# Prototyp-V-0_2.net
KiCad netlist of a schematic drawn in EAGLE
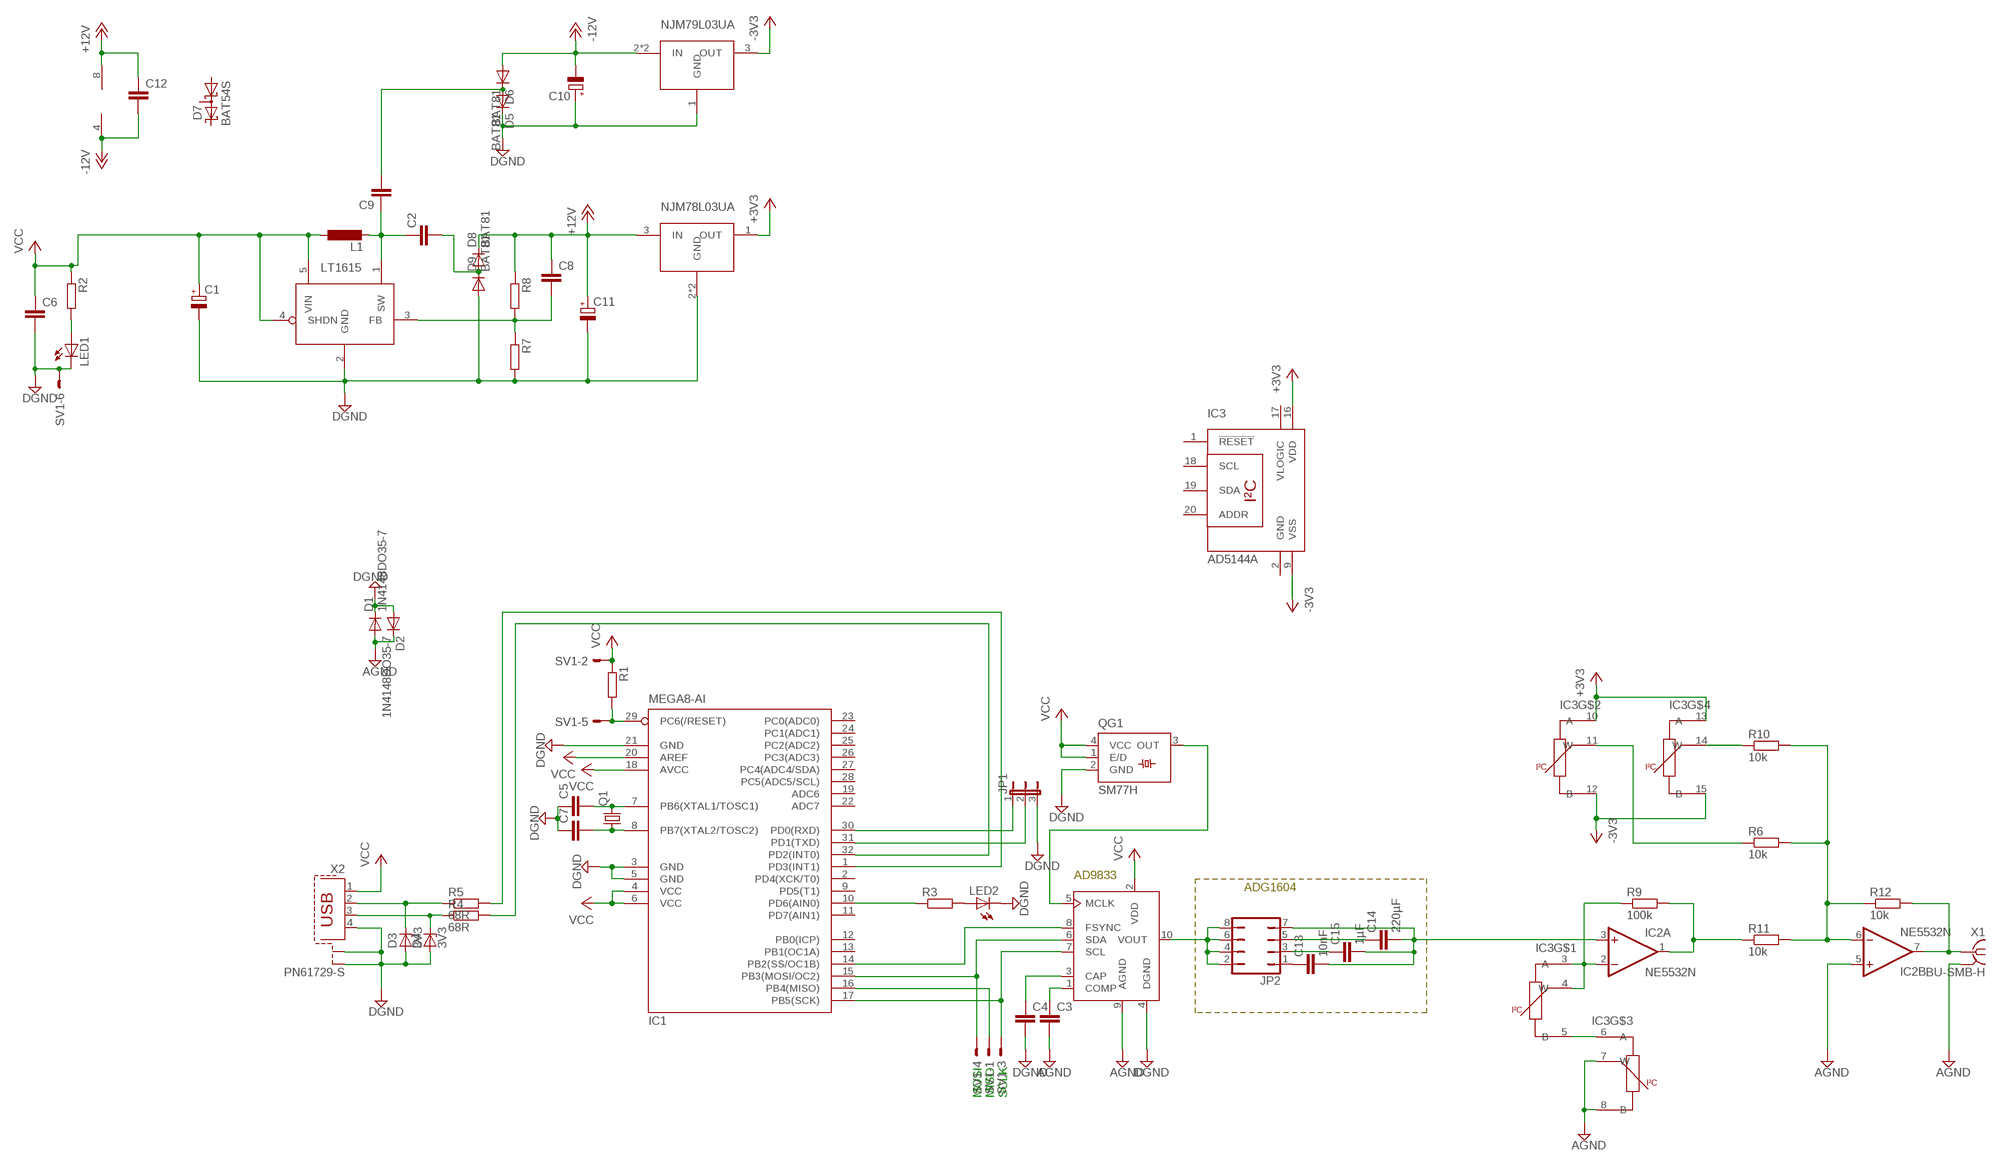
[diagram p0: schematic, sheet 1]

(export (version "E")
  (design (tool "Eeschema 10.0.6"))
  (components
    (comp (ref "C1")
      (value "CPOL-EUE3.5-8")
      (footprint "eagle-import:E3,5-8")
      (libsource (lib "eagle-import") (part "CPOL-EUE3.5-8"))
    )
    (comp (ref "C2")
      (value "C-EU025-024X044")
      (footprint "eagle-import:C025-024X044")
      (libsource (lib "eagle-import") (part "C-EU025-024X044"))
    )
    (comp (ref "C3")
      (value "C-EU025-024X044")
      (footprint "eagle-import:C025-024X044")
      (libsource (lib "eagle-import") (part "C-EU025-024X044"))
    )
    (comp (ref "C4")
      (value "C-EU025-024X044")
      (footprint "eagle-import:C025-024X044")
      (libsource (lib "eagle-import") (part "C-EU025-024X044"))
    )
    (comp (ref "C5")
      (value "C-EU025-024X044")
      (footprint "eagle-import:C025-024X044")
      (libsource (lib "eagle-import") (part "C-EU025-024X044"))
    )
    (comp (ref "C6")
      (value "C-EU025-024X044")
      (footprint "eagle-import:C025-024X044")
      (libsource (lib "eagle-import") (part "C-EU025-024X044"))
    )
    (comp (ref "C7")
      (value "C-EU025-024X044")
      (footprint "eagle-import:C025-024X044")
      (libsource (lib "eagle-import") (part "C-EU025-024X044"))
    )
    (comp (ref "C8")
      (value "C-EU025-024X044")
      (footprint "eagle-import:C025-024X044")
      (libsource (lib "eagle-import") (part "C-EU025-024X044"))
    )
    (comp (ref "C9")
      (value "C-EU025-024X044")
      (footprint "eagle-import:C025-024X044")
      (libsource (lib "eagle-import") (part "C-EU025-024X044"))
    )
    (comp (ref "C10")
      (value "CPOL-EUE3.5-8")
      (footprint "eagle-import:E3,5-8")
      (libsource (lib "eagle-import") (part "CPOL-EUE3.5-8"))
    )
    (comp (ref "C11")
      (value "CPOL-EUE3.5-8")
      (footprint "eagle-import:E3,5-8")
      (libsource (lib "eagle-import") (part "CPOL-EUE3.5-8"))
    )
    (comp (ref "C12")
      (value "C-EU025-024X044")
      (footprint "eagle-import:C025-024X044")
      (libsource (lib "eagle-import") (part "C-EU025-024X044"))
    )
    (comp (ref "C13")
      (value "10nF")
      (footprint "eagle-import:C025-024X044")
      (libsource (lib "eagle-import") (part "C-EU025-024X044"))
    )
    (comp (ref "C14")
      (value "220µF")
      (footprint "eagle-import:C025-024X044")
      (libsource (lib "eagle-import") (part "C-EU025-024X044"))
    )
    (comp (ref "C15")
      (value "1µF")
      (footprint "eagle-import:C025-024X044")
      (libsource (lib "eagle-import") (part "C-EU025-024X044"))
    )
    (comp (ref "D1")
      (value "1N4148DO35-7")
      (footprint "eagle-import:DO35-7")
      (libsource (lib "eagle-import") (part "1N4148DO35-7"))
    )
    (comp (ref "D2")
      (value "1N4148DO35-7")
      (footprint "eagle-import:DO35-7")
      (libsource (lib "eagle-import") (part "1N4148DO35-7"))
    )
    (comp (ref "D3")
      (value "3V3")
      (footprint "eagle-import:ZDIO-7.5")
      (libsource (lib "eagle-import") (part "ZENER-DIODEZD-7.5"))
    )
    (comp (ref "D4")
      (value "3V3")
      (footprint "eagle-import:ZDIO-7.5")
      (libsource (lib "eagle-import") (part "ZENER-DIODEZD-7.5"))
    )
    (comp (ref "D5")
      (value "BAT81")
      (footprint "eagle-import:DO34-7")
      (libsource (lib "eagle-import") (part "BAT81"))
    )
    (comp (ref "D6")
      (value "BAT81")
      (footprint "eagle-import:DO34-7")
      (libsource (lib "eagle-import") (part "BAT81"))
    )
    (comp (ref "D7")
      (value "BAT54S")
      (footprint "eagle-import:SOT23")
      (libsource (lib "eagle-import") (part "BAT54S"))
    )
    (comp (ref "D8")
      (value "BAT81")
      (footprint "eagle-import:DO34-7")
      (libsource (lib "eagle-import") (part "BAT81"))
    )
    (comp (ref "D9")
      (value "BAT81")
      (footprint "eagle-import:DO34-7")
      (libsource (lib "eagle-import") (part "BAT81"))
    )
    (comp (ref "IC1")
      (value "MEGA8-AI")
      (footprint "eagle-import:TQFP32-08")
      (fields (field (name "MPN") "ATMEGA8-16AU"))
      (libsource (lib "eagle-import") (part "MEGA8-AI"))
    )
    (comp (ref "IC2")
      (value "NE5532N")
      (footprint "eagle-import:DIL08")
      (libsource (lib "eagle-import") (part "NE5532N"))
    )
    (comp (ref "IC3")
      (value "AD5144A")
      (footprint "eagle-import:TSSOP20")
      (libsource (lib "eagle-import") (part "AD5144A"))
    )
    (comp (ref "JP1")
      (value "JP2E")
      (footprint "eagle-import:JP2")
      (libsource (lib "eagle-import") (part "JP2E"))
    )
    (comp (ref "JP2")
      (value "JP4Q")
      (footprint "eagle-import:JP4Q")
      (libsource (lib "eagle-import") (part "JP4Q"))
    )
    (comp (ref "L1")
      (value "L-EU0207/10")
      (footprint "eagle-import:0207_10")
      (libsource (lib "eagle-import") (part "L-EU0207/10"))
    )
    (comp (ref "LED1")
      (value "LED5MM")
      (footprint "eagle-import:LED5MM")
      (libsource (lib "eagle-import") (part "LED5MM"))
    )
    (comp (ref "LED2")
      (value "LED5MM")
      (footprint "eagle-import:LED5MM")
      (libsource (lib "eagle-import") (part "LED5MM"))
    )
    (comp (ref "Q1")
      (value "CRYSTALSM77H")
      (footprint "eagle-import:SM77H")
      (libsource (lib "eagle-import") (part "CRYSTALSM77H"))
    )
    (comp (ref "QG1")
      (value "SM77H")
      (footprint "eagle-import:SM77H")
      (libsource (lib "eagle-import") (part "SM77H"))
    )
    (comp (ref "R1")
      (value "R-EU_0207/10")
      (footprint "eagle-import:0207_10")
      (libsource (lib "eagle-import") (part "R-EU_0207/10"))
    )
    (comp (ref "R2")
      (value "R-EU_0207/10")
      (footprint "eagle-import:0207_10")
      (libsource (lib "eagle-import") (part "R-EU_0207/10"))
    )
    (comp (ref "R3")
      (value "R-EU_0207/10")
      (footprint "eagle-import:0207_10")
      (libsource (lib "eagle-import") (part "R-EU_0207/10"))
    )
    (comp (ref "R4")
      (value "68R")
      (footprint "eagle-import:0207_10")
      (libsource (lib "eagle-import") (part "R-EU_0207/10"))
    )
    (comp (ref "R5")
      (value "68R")
      (footprint "eagle-import:0207_10")
      (libsource (lib "eagle-import") (part "R-EU_0207/10"))
    )
    (comp (ref "R6")
      (value "10k")
      (footprint "eagle-import:0207_10")
      (libsource (lib "eagle-import") (part "R-EU_0207/10"))
    )
    (comp (ref "R7")
      (value "R-EU_0207/10")
      (footprint "eagle-import:0207_10")
      (libsource (lib "eagle-import") (part "R-EU_0207/10"))
    )
    (comp (ref "R8")
      (value "R-EU_0207/10")
      (footprint "eagle-import:0207_10")
      (libsource (lib "eagle-import") (part "R-EU_0207/10"))
    )
    (comp (ref "R9")
      (value "100k")
      (footprint "eagle-import:0207_10")
      (libsource (lib "eagle-import") (part "R-EU_0207/10"))
    )
    (comp (ref "R10")
      (value "10k")
      (footprint "eagle-import:0207_10")
      (libsource (lib "eagle-import") (part "R-EU_0207/10"))
    )
    (comp (ref "R11")
      (value "10k")
      (footprint "eagle-import:0207_10")
      (libsource (lib "eagle-import") (part "R-EU_0207/10"))
    )
    (comp (ref "R12")
      (value "10k")
      (footprint "eagle-import:0207_10")
      (libsource (lib "eagle-import") (part "R-EU_0207/10"))
    )
    (comp (ref "SV1")
      (value "ML6E")
      (footprint "eagle-import:ML6")
      (libsource (lib "eagle-import") (part "ML6?E"))
    )
    (comp (ref "U$1")
      (value "AD9833-P")
      (footprint "eagle-import:DIL10")
      (libsource (lib "eagle-import") (part "AD9833-P"))
    )
    (comp (ref "U$2")
      (value "LT1615")
      (footprint "eagle-import:SOT23-5")
      (libsource (lib "eagle-import") (part "LT1615"))
    )
    (comp (ref "U$3")
      (value "NJM79L03UA")
      (footprint "eagle-import:SOT89")
      (libsource (lib "eagle-import") (part "NJM79L03UA"))
    )
    (comp (ref "U$4")
      (value "NJM78L03UA")
      (footprint "eagle-import:SOT89")
      (libsource (lib "eagle-import") (part "NJM78L03UA"))
    )
    (comp (ref "X1")
      (value "BU-SMB-H")
      (footprint "eagle-import:BU-SMB-H")
      (libsource (lib "eagle-import") (part "BU-SMB-H"))
    )
    (comp (ref "X2")
      (value "PN61729-S")
      (footprint "eagle-import:PN61729-S")
      (libsource (lib "eagle-import") (part "PN61729-S"))
    )
  )
  (nets
    (net (code "1") (name "+3V3") (class "Default")
      (node (ref "IC3") (pin "10") (pinfunction "A_10") (pintype "bidirectional"))
      (node (ref "IC3") (pin "13") (pinfunction "A_13") (pintype "bidirectional"))
      (node (ref "IC3") (pin "16") (pinfunction "VDD_16") (pintype "bidirectional"))
      (node (ref "U$4") (pin "1") (pinfunction "OUT_1") (pintype "bidirectional"))
    )
    (net (code "2") (name "+12V") (class "Default")
      (node (ref "C11") (pin "+") (pinfunction "+_+") (pintype "passive"))
      (node (ref "C12") (pin "1") (pinfunction "1_1") (pintype "passive"))
      (node (ref "C8") (pin "1") (pinfunction "1_1") (pintype "passive"))
      (node (ref "D8") (pin "C") (pinfunction "C_C") (pintype "passive"))
      (node (ref "IC2") (pin "8") (pinfunction "V+_8") (pintype "power_in"))
      (node (ref "R8") (pin "1") (pinfunction "1_1") (pintype "passive"))
      (node (ref "U$4") (pin "3") (pinfunction "IN_3") (pintype "bidirectional"))
    )
    (net (code "3") (name "-3V3") (class "Default")
      (node (ref "IC3") (pin "12") (pinfunction "B_12") (pintype "bidirectional"))
      (node (ref "IC3") (pin "15") (pinfunction "B_15") (pintype "bidirectional"))
      (node (ref "IC3") (pin "9") (pinfunction "VSS_9") (pintype "bidirectional"))
      (node (ref "U$3") (pin "3") (pinfunction "OUT_3") (pintype "bidirectional"))
    )
    (net (code "4") (name "-12V") (class "Default")
      (node (ref "C10") (pin "-") (pinfunction "-_-") (pintype "passive"))
      (node (ref "C12") (pin "2") (pinfunction "2_2") (pintype "passive"))
      (node (ref "D6") (pin "A") (pinfunction "A_A") (pintype "passive"))
      (node (ref "IC2") (pin "4") (pinfunction "V-_4") (pintype "power_in"))
      (node (ref "U$3") (pin "2") (pinfunction "IN_2") (pintype "bidirectional"))
      (node (ref "U$3") (pin "2@1") (pinfunction "IN_2@1") (pintype "bidirectional"))
    )
    (net (code "5") (name "AGND") (class "Default")
      (node (ref "C3") (pin "2") (pinfunction "2_2") (pintype "passive"))
      (node (ref "D1") (pin "A") (pinfunction "A_A") (pintype "passive"))
      (node (ref "D2") (pin "C") (pinfunction "C_C") (pintype "passive"))
      (node (ref "IC2") (pin "5") (pinfunction "+IN_5") (pintype "input"))
      (node (ref "IC3") (pin "7") (pinfunction "W_7") (pintype "bidirectional"))
      (node (ref "IC3") (pin "8") (pinfunction "B_8") (pintype "bidirectional"))
      (node (ref "U$1") (pin "9") (pinfunction "AGND_9") (pintype "bidirectional"))
      (node (ref "X1") (pin "2") (pinfunction "2_2") (pintype "passive"))
      (node (ref "X1") (pin "3") (pinfunction "2_3") (pintype "passive"))
      (node (ref "X1") (pin "4") (pinfunction "2_4") (pintype "passive"))
      (node (ref "X1") (pin "5") (pinfunction "2_5") (pintype "passive"))
    )
    (net (code "6") (name "DGND") (class "Default")
      (node (ref "C1") (pin "-") (pinfunction "-_-") (pintype "passive"))
      (node (ref "C10") (pin "+") (pinfunction "+_+") (pintype "passive"))
      (node (ref "C11") (pin "-") (pinfunction "-_-") (pintype "passive"))
      (node (ref "C4") (pin "2") (pinfunction "2_2") (pintype "passive"))
      (node (ref "C5") (pin "1") (pinfunction "1_1") (pintype "passive"))
      (node (ref "C6") (pin "2") (pinfunction "2_2") (pintype "passive"))
      (node (ref "C7") (pin "1") (pinfunction "1_1") (pintype "passive"))
      (node (ref "D1") (pin "C") (pinfunction "C_C") (pintype "passive"))
      (node (ref "D2") (pin "A") (pinfunction "A_A") (pintype "passive"))
      (node (ref "D3") (pin "A") (pinfunction "A_A") (pintype "passive"))
      (node (ref "D4") (pin "A") (pinfunction "A_A") (pintype "passive"))
      (node (ref "D5") (pin "C") (pinfunction "C_C") (pintype "passive"))
      (node (ref "D9") (pin "A") (pinfunction "A_A") (pintype "passive"))
      (node (ref "IC1") (pin "21") (pinfunction "GND_21") (pintype "power_in"))
      (node (ref "IC1") (pin "3") (pinfunction "GND_3") (pintype "power_in"))
      (node (ref "IC1") (pin "5") (pinfunction "GND_5") (pintype "power_in"))
      (node (ref "JP1") (pin "3") (pinfunction "3_3") (pintype "passive"))
      (node (ref "LED1") (pin "K") (pinfunction "C_K") (pintype "passive"))
      (node (ref "LED2") (pin "K") (pinfunction "C_K") (pintype "passive"))
      (node (ref "QG1") (pin "2") (pinfunction "GND_2") (pintype "power_in"))
      (node (ref "R7") (pin "2") (pinfunction "2_2") (pintype "passive"))
      (node (ref "SV1") (pin "6") (pinfunction "S_6") (pintype "passive"))
      (node (ref "U$1") (pin "4") (pinfunction "DGND_4") (pintype "bidirectional"))
      (node (ref "U$2") (pin "2") (pinfunction "GND_2") (pintype "bidirectional"))
      (node (ref "U$3") (pin "1") (pinfunction "GND_1") (pintype "bidirectional"))
      (node (ref "U$4") (pin "2") (pinfunction "GND_2") (pintype "bidirectional"))
      (node (ref "U$4") (pin "2@1") (pinfunction "GND_2@1") (pintype "bidirectional"))
      (node (ref "X2") (pin "4") (pinfunction "4_4") (pintype "passive"))
      (node (ref "X2") (pin "S1") (pinfunction "S1_S1") (pintype "passive"))
      (node (ref "X2") (pin "S2") (pinfunction "S2_S2") (pintype "passive"))
    )
    (net (code "7") (name "Net-(C2-Pad2)") (class "Default")
      (node (ref "C2") (pin "2") (pinfunction "2_2") (pintype "passive"))
      (node (ref "D8") (pin "A") (pinfunction "A_A") (pintype "passive"))
      (node (ref "D9") (pin "C") (pinfunction "C_C") (pintype "passive"))
    )
    (net (code "8") (name "Net-(C9-Pad2)") (class "Default")
      (node (ref "C9") (pin "2") (pinfunction "2_2") (pintype "passive"))
      (node (ref "D5") (pin "A") (pinfunction "A_A") (pintype "passive"))
      (node (ref "D6") (pin "C") (pinfunction "C_C") (pintype "passive"))
    )
    (net (code "9") (name "Net-(C13-Pad1)") (class "Default")
      (node (ref "C13") (pin "1") (pinfunction "1_1") (pintype "passive"))
      (node (ref "JP2") (pin "1") (pinfunction "1_1") (pintype "passive"))
    )
    (net (code "10") (name "Net-(C14-Pad1)") (class "Default")
      (node (ref "C14") (pin "1") (pinfunction "1_1") (pintype "passive"))
      (node (ref "JP2") (pin "5") (pinfunction "5_5") (pintype "passive"))
    )
    (net (code "11") (name "Net-(C15-Pad1)") (class "Default")
      (node (ref "C15") (pin "1") (pinfunction "1_1") (pintype "passive"))
      (node (ref "JP2") (pin "3") (pinfunction "3_3") (pintype "passive"))
    )
    (net (code "12") (name "Net-(D3-PadC)") (class "Default")
      (node (ref "D3") (pin "C") (pinfunction "C_C") (pintype "passive"))
      (node (ref "R5") (pin "1") (pinfunction "1_1") (pintype "passive"))
      (node (ref "X2") (pin "2") (pinfunction "2_2") (pintype "passive"))
    )
    (net (code "13") (name "Net-(D4-PadC)") (class "Default")
      (node (ref "D4") (pin "C") (pinfunction "C_C") (pintype "passive"))
      (node (ref "R4") (pin "1") (pinfunction "1_1") (pintype "passive"))
      (node (ref "X2") (pin "3") (pinfunction "3_3") (pintype "passive"))
    )
    (net (code "14") (name "Net-(IC1-PB2(SS{slash}OC1B))") (class "Default")
      (node (ref "IC1") (pin "14") (pinfunction "PB2(SS/OC1B)_14") (pintype "bidirectional"))
      (node (ref "U$1") (pin "8") (pinfunction "FSYNC_8") (pintype "bidirectional"))
    )
    (net (code "15") (name "Net-(IC1-PB3(MOSI{slash}OC2))") (class "Default")
      (node (ref "IC1") (pin "15") (pinfunction "PB3(MOSI/OC2)_15") (pintype "bidirectional"))
      (node (ref "SV1") (pin "4") (pinfunction "S_4") (pintype "passive"))
      (node (ref "U$1") (pin "6") (pinfunction "SDA_6") (pintype "bidirectional"))
    )
    (net (code "16") (name "Net-(IC1-PB4(MISO))") (class "Default")
      (node (ref "IC1") (pin "16") (pinfunction "PB4(MISO)_16") (pintype "bidirectional"))
      (node (ref "SV1") (pin "1") (pinfunction "S_1") (pintype "passive"))
    )
    (net (code "17") (name "Net-(IC1-PB5(SCK))") (class "Default")
      (node (ref "IC1") (pin "17") (pinfunction "PB5(SCK)_17") (pintype "bidirectional"))
      (node (ref "SV1") (pin "3") (pinfunction "S_3") (pintype "passive"))
      (node (ref "U$1") (pin "7") (pinfunction "SCL_7") (pintype "bidirectional"))
    )
    (net (code "18") (name "Net-(IC1-PB6(XTAL1{slash}TOSC1))") (class "Default")
      (node (ref "C5") (pin "2") (pinfunction "2_2") (pintype "passive"))
      (node (ref "IC1") (pin "7") (pinfunction "PB6(XTAL1/TOSC1)_7") (pintype "bidirectional"))
      (node (ref "Q1") (pin "3") (pinfunction "2_3") (pintype "passive"))
    )
    (net (code "19") (name "Net-(IC1-PB7(XTAL2{slash}TOSC2))") (class "Default")
      (node (ref "C7") (pin "2") (pinfunction "2_2") (pintype "passive"))
      (node (ref "IC1") (pin "8") (pinfunction "PB7(XTAL2/TOSC2)_8") (pintype "bidirectional"))
      (node (ref "Q1") (pin "1") (pinfunction "1_1") (pintype "passive"))
    )
    (net (code "20") (name "Net-(IC1-PC6({slash}RESET))") (class "Default")
      (node (ref "IC1") (pin "29") (pinfunction "PC6(/RESET)_29") (pintype "bidirectional"))
      (node (ref "R1") (pin "2") (pinfunction "2_2") (pintype "passive"))
      (node (ref "SV1") (pin "5") (pinfunction "S_5") (pintype "passive"))
    )
    (net (code "21") (name "Net-(IC1-PD0(RXD))") (class "Default")
      (node (ref "IC1") (pin "30") (pinfunction "PD0(RXD)_30") (pintype "bidirectional"))
      (node (ref "JP1") (pin "1") (pinfunction "1_1") (pintype "passive"))
    )
    (net (code "22") (name "Net-(IC1-PD1(TXD))") (class "Default")
      (node (ref "IC1") (pin "31") (pinfunction "PD1(TXD)_31") (pintype "bidirectional"))
      (node (ref "JP1") (pin "2") (pinfunction "2_2") (pintype "passive"))
    )
    (net (code "23") (name "Net-(IC1-PD2(INT0))") (class "Default")
      (node (ref "IC1") (pin "32") (pinfunction "PD2(INT0)_32") (pintype "bidirectional"))
      (node (ref "R4") (pin "2") (pinfunction "2_2") (pintype "passive"))
    )
    (net (code "24") (name "Net-(IC1-PD3(INT1))") (class "Default")
      (node (ref "IC1") (pin "1") (pinfunction "PD3(INT1)_1") (pintype "bidirectional"))
      (node (ref "R5") (pin "2") (pinfunction "2_2") (pintype "passive"))
    )
    (net (code "25") (name "Net-(IC1-PD6(AIN0))") (class "Default")
      (node (ref "IC1") (pin "10") (pinfunction "PD6(AIN0)_10") (pintype "bidirectional"))
      (node (ref "R3") (pin "1") (pinfunction "1_1") (pintype "passive"))
    )
    (net (code "26") (name "Net-(IC2A-+IN)") (class "Default")
      (node (ref "C13") (pin "2") (pinfunction "2_2") (pintype "passive"))
      (node (ref "C14") (pin "2") (pinfunction "2_2") (pintype "passive"))
      (node (ref "C15") (pin "2") (pinfunction "2_2") (pintype "passive"))
      (node (ref "IC2") (pin "3") (pinfunction "+IN_3") (pintype "input"))
      (node (ref "JP2") (pin "7") (pinfunction "7_7") (pintype "passive"))
    )
    (net (code "27") (name "Net-(IC2A--IN)") (class "Default")
      (node (ref "IC2") (pin "2") (pinfunction "-IN_2") (pintype "input"))
      (node (ref "IC3") (pin "3") (pinfunction "A_3") (pintype "bidirectional"))
      (node (ref "IC3") (pin "4") (pinfunction "W_4") (pintype "bidirectional"))
      (node (ref "R9") (pin "1") (pinfunction "1_1") (pintype "passive"))
    )
    (net (code "28") (name "Net-(IC2A-OUT)") (class "Default")
      (node (ref "IC2") (pin "1") (pinfunction "OUT_1") (pintype "output"))
      (node (ref "R11") (pin "1") (pinfunction "1_1") (pintype "passive"))
      (node (ref "R9") (pin "2") (pinfunction "2_2") (pintype "passive"))
    )
    (net (code "29") (name "Net-(IC2B--IN)") (class "Default")
      (node (ref "IC2") (pin "6") (pinfunction "-IN_6") (pintype "input"))
      (node (ref "R10") (pin "2") (pinfunction "2_2") (pintype "passive"))
      (node (ref "R11") (pin "2") (pinfunction "2_2") (pintype "passive"))
      (node (ref "R12") (pin "1") (pinfunction "1_1") (pintype "passive"))
      (node (ref "R6") (pin "2") (pinfunction "2_2") (pintype "passive"))
    )
    (net (code "30") (name "Net-(IC2B-OUT)") (class "Default")
      (node (ref "IC2") (pin "7") (pinfunction "OUT_7") (pintype "output"))
      (node (ref "R12") (pin "2") (pinfunction "2_2") (pintype "passive"))
      (node (ref "X1") (pin "1") (pinfunction "1_1") (pintype "passive"))
    )
    (net (code "31") (name "Net-(IC3A-B)") (class "Default")
      (node (ref "IC3") (pin "5") (pinfunction "B_5") (pintype "bidirectional"))
      (node (ref "IC3") (pin "6") (pinfunction "A_6") (pintype "bidirectional"))
    )
    (net (code "32") (name "Net-(IC3B-W)") (class "Default")
      (node (ref "IC3") (pin "11") (pinfunction "W_11") (pintype "bidirectional"))
      (node (ref "R6") (pin "1") (pinfunction "1_1") (pintype "passive"))
    )
    (net (code "33") (name "Net-(IC3D-W)") (class "Default")
      (node (ref "IC3") (pin "14") (pinfunction "W_14") (pintype "bidirectional"))
      (node (ref "R10") (pin "1") (pinfunction "1_1") (pintype "passive"))
    )
    (net (code "34") (name "Net-(LED1-PadA)") (class "Default")
      (node (ref "LED1") (pin "A") (pinfunction "A_A") (pintype "passive"))
      (node (ref "R2") (pin "2") (pinfunction "2_2") (pintype "passive"))
    )
    (net (code "35") (name "Net-(LED2-PadA)") (class "Default")
      (node (ref "LED2") (pin "A") (pinfunction "A_A") (pintype "passive"))
      (node (ref "R3") (pin "2") (pinfunction "2_2") (pintype "passive"))
    )
    (net (code "36") (name "Net-(QG1-OUT)") (class "Default")
      (node (ref "QG1") (pin "3") (pinfunction "OUT_3") (pintype "output"))
      (node (ref "U$1") (pin "5") (pinfunction "MCLK_5") (pintype "bidirectional"))
    )
    (net (code "37") (name "Net-(U$1-CAP)") (class "Default")
      (node (ref "C4") (pin "1") (pinfunction "1_1") (pintype "passive"))
      (node (ref "U$1") (pin "3") (pinfunction "CAP_3") (pintype "bidirectional"))
    )
    (net (code "38") (name "Net-(U$1-COMP)") (class "Default")
      (node (ref "C3") (pin "1") (pinfunction "1_1") (pintype "passive"))
      (node (ref "U$1") (pin "1") (pinfunction "COMP_1") (pintype "bidirectional"))
    )
    (net (code "39") (name "Net-(U$1-VOUT)") (class "Default")
      (node (ref "JP2") (pin "2") (pinfunction "2_2") (pintype "passive"))
      (node (ref "JP2") (pin "4") (pinfunction "4_4") (pintype "passive"))
      (node (ref "JP2") (pin "6") (pinfunction "6_6") (pintype "passive"))
      (node (ref "JP2") (pin "8") (pinfunction "8_8") (pintype "passive"))
      (node (ref "U$1") (pin "10") (pinfunction "VOUT_10") (pintype "bidirectional"))
    )
    (net (code "40") (name "Net-(U$2-FB)") (class "Default")
      (node (ref "C8") (pin "2") (pinfunction "2_2") (pintype "passive"))
      (node (ref "R7") (pin "1") (pinfunction "1_1") (pintype "passive"))
      (node (ref "R8") (pin "2") (pinfunction "2_2") (pintype "passive"))
      (node (ref "U$2") (pin "3") (pinfunction "FB_3") (pintype "bidirectional"))
    )
    (net (code "41") (name "Net-(U$2-SW)") (class "Default")
      (node (ref "C2") (pin "1") (pinfunction "1_1") (pintype "passive"))
      (node (ref "C9") (pin "1") (pinfunction "1_1") (pintype "passive"))
      (node (ref "L1") (pin "2") (pinfunction "2_2") (pintype "passive"))
      (node (ref "U$2") (pin "1") (pinfunction "SW_1") (pintype "bidirectional"))
    )
    (net (code "42") (name "VCC") (class "Default")
      (node (ref "C1") (pin "+") (pinfunction "+_+") (pintype "passive"))
      (node (ref "C6") (pin "1") (pinfunction "1_1") (pintype "passive"))
      (node (ref "IC1") (pin "18") (pinfunction "AVCC_18") (pintype "power_in"))
      (node (ref "IC1") (pin "20") (pinfunction "AREF_20") (pintype "passive"))
      (node (ref "IC1") (pin "4") (pinfunction "VCC_4") (pintype "power_in"))
      (node (ref "IC1") (pin "6") (pinfunction "VCC_6") (pintype "power_in"))
      (node (ref "L1") (pin "1") (pinfunction "1_1") (pintype "passive"))
      (node (ref "QG1") (pin "1") (pinfunction "E/D_1") (pintype "input"))
      (node (ref "QG1") (pin "4") (pinfunction "VCC_4") (pintype "power_in"))
      (node (ref "R1") (pin "1") (pinfunction "1_1") (pintype "passive"))
      (node (ref "R2") (pin "1") (pinfunction "1_1") (pintype "passive"))
      (node (ref "SV1") (pin "2") (pinfunction "S_2") (pintype "passive"))
      (node (ref "U$1") (pin "2") (pinfunction "VDD_2") (pintype "bidirectional"))
      (node (ref "U$2") (pin "4") (pinfunction "SHDN_4") (pintype "bidirectional"))
      (node (ref "U$2") (pin "5") (pinfunction "VIN_5") (pintype "bidirectional"))
      (node (ref "X2") (pin "1") (pinfunction "1_1") (pintype "passive"))
    )
    (net (code "43") (name "unconnected-(D7-A1-Pad1)") (class "Default")
      (node (ref "D7") (pin "1") (pinfunction "A1_1") (pintype "passive"))
    )
    (net (code "44") (name "unconnected-(D7-C1A2-Pad3)") (class "Default")
      (node (ref "D7") (pin "3") (pinfunction "C1A2_3") (pintype "passive"))
    )
    (net (code "45") (name "unconnected-(D7-C2-Pad2)") (class "Default")
      (node (ref "D7") (pin "2") (pinfunction "C2_2") (pintype "passive"))
    )
    (net (code "46") (name "unconnected-(IC1-ADC6-Pad19)") (class "Default")
      (node (ref "IC1") (pin "19") (pinfunction "ADC6_19") (pintype "bidirectional"))
    )
    (net (code "47") (name "unconnected-(IC1-ADC7-Pad22)") (class "Default")
      (node (ref "IC1") (pin "22") (pinfunction "ADC7_22") (pintype "bidirectional"))
    )
    (net (code "48") (name "unconnected-(IC1-PB0(ICP)-Pad12)") (class "Default")
      (node (ref "IC1") (pin "12") (pinfunction "PB0(ICP)_12") (pintype "bidirectional"))
    )
    (net (code "49") (name "unconnected-(IC1-PB1(OC1A)-Pad13)") (class "Default")
      (node (ref "IC1") (pin "13") (pinfunction "PB1(OC1A)_13") (pintype "bidirectional"))
    )
    (net (code "50") (name "unconnected-(IC1-PC0(ADC0)-Pad23)") (class "Default")
      (node (ref "IC1") (pin "23") (pinfunction "PC0(ADC0)_23") (pintype "bidirectional"))
    )
    (net (code "51") (name "unconnected-(IC1-PC1(ADC1)-Pad24)") (class "Default")
      (node (ref "IC1") (pin "24") (pinfunction "PC1(ADC1)_24") (pintype "bidirectional"))
    )
    (net (code "52") (name "unconnected-(IC1-PC2(ADC2)-Pad25)") (class "Default")
      (node (ref "IC1") (pin "25") (pinfunction "PC2(ADC2)_25") (pintype "bidirectional"))
    )
    (net (code "53") (name "unconnected-(IC1-PC3(ADC3)-Pad26)") (class "Default")
      (node (ref "IC1") (pin "26") (pinfunction "PC3(ADC3)_26") (pintype "bidirectional"))
    )
    (net (code "54") (name "unconnected-(IC1-PC4(ADC4{slash}SDA)-Pad27)") (class "Default")
      (node (ref "IC1") (pin "27") (pinfunction "PC4(ADC4/SDA)_27") (pintype "bidirectional"))
    )
    (net (code "55") (name "unconnected-(IC1-PC5(ADC5{slash}SCL)-Pad28)") (class "Default")
      (node (ref "IC1") (pin "28") (pinfunction "PC5(ADC5/SCL)_28") (pintype "bidirectional"))
    )
    (net (code "56") (name "unconnected-(IC1-PD4(XCK{slash}T0)-Pad2)") (class "Default")
      (node (ref "IC1") (pin "2") (pinfunction "PD4(XCK/T0)_2") (pintype "bidirectional"))
    )
    (net (code "57") (name "unconnected-(IC1-PD5(T1)-Pad9)") (class "Default")
      (node (ref "IC1") (pin "9") (pinfunction "PD5(T1)_9") (pintype "bidirectional"))
    )
    (net (code "58") (name "unconnected-(IC1-PD7(AIN1)-Pad11)") (class "Default")
      (node (ref "IC1") (pin "11") (pinfunction "PD7(AIN1)_11") (pintype "bidirectional"))
    )
    (net (code "59") (name "unconnected-(IC3E-ADDR-Pad20)") (class "Default")
      (node (ref "IC3") (pin "20") (pinfunction "ADDR_20") (pintype "bidirectional"))
    )
    (net (code "60") (name "unconnected-(IC3E-GND-Pad2)") (class "Default")
      (node (ref "IC3") (pin "2") (pinfunction "GND_2") (pintype "bidirectional"))
    )
    (net (code "61") (name "unconnected-(IC3E-SCL-Pad18)") (class "Default")
      (node (ref "IC3") (pin "18") (pinfunction "SCL_18") (pintype "bidirectional"))
    )
    (net (code "62") (name "unconnected-(IC3E-SDA-Pad19)") (class "Default")
      (node (ref "IC3") (pin "19") (pinfunction "SDA_19") (pintype "bidirectional"))
    )
    (net (code "63") (name "unconnected-(IC3E-VLOGIC-Pad17)") (class "Default")
      (node (ref "IC3") (pin "17") (pinfunction "VLOGIC_17") (pintype "bidirectional"))
    )
    (net (code "64") (name "unconnected-(IC3E-~{RESET}-Pad1)") (class "Default")
      (node (ref "IC3") (pin "1") (pinfunction "~{RESET}_1") (pintype "bidirectional"))
    )
  )
)
